# SDP_2.net
KiCad netlist of a schematic drawn in Altium Designer
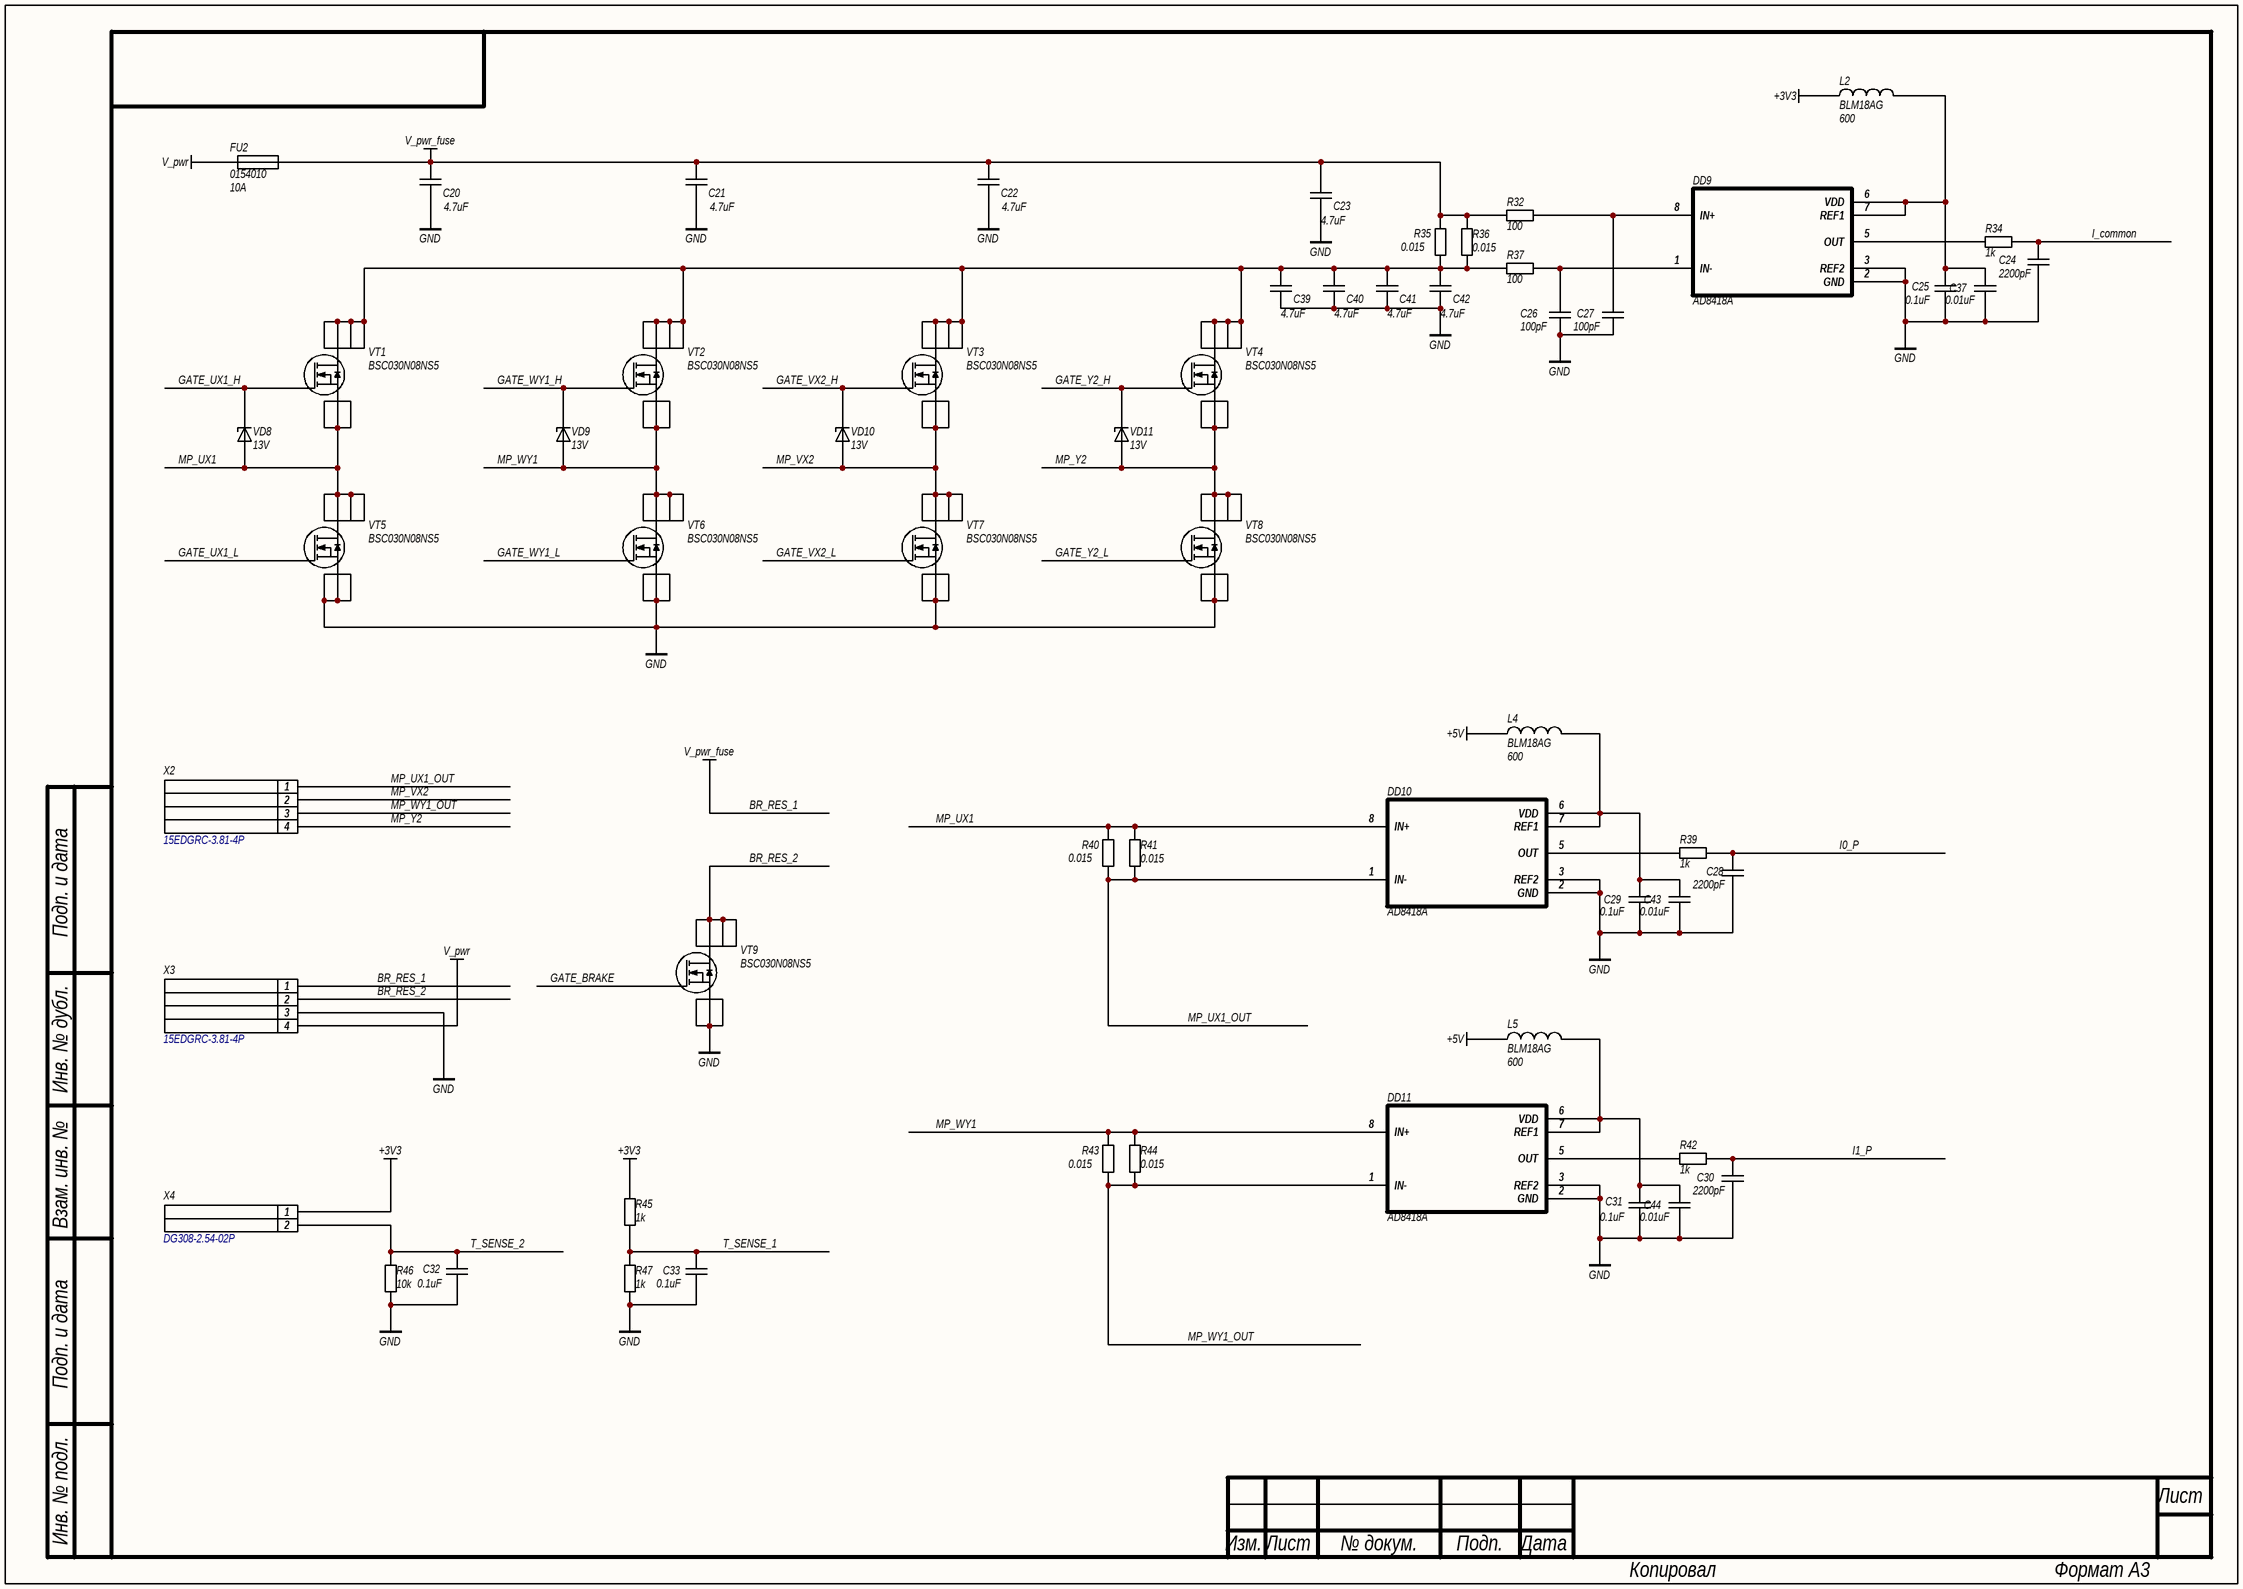
[diagram p0: SDP_2.SchDoc]

(export (version "E")
  (design (tool "Eeschema 10.0.6"))
  (components
    (comp (ref "C20")
      (value "4.7uF")
      (footprint "C1210")
      (description "SMD Capacitor")
      (fields (field (name "MANUFACTURER") "Murata") (field (name "TOLERANCE") "10%"))
      (libsource (lib "VKA") (part "CAP"))
    )
    (comp (ref "C21")
      (value "4.7uF")
      (footprint "C1210")
      (description "SMD Capacitor")
      (fields (field (name "MANUFACTURER") "Murata") (field (name "TOLERANCE") "10%"))
      (libsource (lib "VKA") (part "CAP"))
    )
    (comp (ref "C22")
      (value "4.7uF")
      (footprint "C1210")
      (description "SMD Capacitor")
      (fields (field (name "MANUFACTURER") "Murata") (field (name "TOLERANCE") "10%"))
      (libsource (lib "VKA") (part "CAP"))
    )
    (comp (ref "C23")
      (value "4.7uF")
      (footprint "C1210")
      (description "SMD Capacitor")
      (fields (field (name "MANUFACTURER") "Murata") (field (name "TOLERANCE") "10%"))
      (libsource (lib "VKA") (part "CAP"))
    )
    (comp (ref "C24")
      (value "2200pF")
      (footprint "C0603")
      (description "SMD Capacitor")
      (fields (field (name "MANUFACTURER") "Murata") (field (name "TOLERANCE") "10%"))
      (libsource (lib "VKA") (part "CAP"))
    )
    (comp (ref "C25")
      (value "0.1uF")
      (footprint "C0603")
      (description "SMD Capacitor")
      (fields (field (name "MANUFACTURER") "Murata") (field (name "TOLERANCE") "10%"))
      (libsource (lib "VKA") (part "CAP"))
    )
    (comp (ref "C26")
      (value "100pF")
      (footprint "C0603")
      (description "SMD Capacitor")
      (fields (field (name "MANUFACTURER") "Murata") (field (name "TOLERANCE") "10%"))
      (libsource (lib "VKA") (part "CAP"))
    )
    (comp (ref "C27")
      (value "100pF")
      (footprint "C0603")
      (description "SMD Capacitor")
      (fields (field (name "MANUFACTURER") "Murata") (field (name "TOLERANCE") "10%"))
      (libsource (lib "VKA") (part "CAP"))
    )
    (comp (ref "C28")
      (value "2200pF")
      (footprint "C0603")
      (description "SMD Capacitor")
      (fields (field (name "MANUFACTURER") "Murata") (field (name "TOLERANCE") "10%"))
      (libsource (lib "VKA") (part "CAP"))
    )
    (comp (ref "C29")
      (value "0.1uF")
      (footprint "C0603")
      (description "SMD Capacitor")
      (fields (field (name "MANUFACTURER") "Murata") (field (name "TOLERANCE") "10%"))
      (libsource (lib "VKA") (part "CAP"))
    )
    (comp (ref "C30")
      (value "2200pF")
      (footprint "C0603")
      (description "SMD Capacitor")
      (fields (field (name "MANUFACTURER") "Murata") (field (name "TOLERANCE") "10%"))
      (libsource (lib "VKA") (part "CAP"))
    )
    (comp (ref "C31")
      (value "0.1uF")
      (footprint "C0603")
      (description "SMD Capacitor")
      (fields (field (name "MANUFACTURER") "Murata") (field (name "TOLERANCE") "10%"))
      (libsource (lib "VKA") (part "CAP"))
    )
    (comp (ref "C32")
      (value "0.1uF")
      (footprint "C0603")
      (description "SMD Capacitor")
      (fields (field (name "MANUFACTURER") "Murata") (field (name "TOLERANCE") "10%"))
      (libsource (lib "VKA") (part "CAP"))
    )
    (comp (ref "C33")
      (value "0.1uF")
      (footprint "C0603")
      (description "SMD Capacitor")
      (fields (field (name "MANUFACTURER") "Murata") (field (name "TOLERANCE") "10%"))
      (libsource (lib "VKA") (part "CAP"))
    )
    (comp (ref "C37")
      (value "0.01uF")
      (footprint "C0603")
      (description "SMD Capacitor")
      (fields (field (name "MANUFACTURER") "Murata") (field (name "TOLERANCE") "10%"))
      (libsource (lib "VKA") (part "CAP"))
    )
    (comp (ref "C39")
      (value "4.7uF")
      (footprint "C1210")
      (description "SMD Capacitor")
      (fields (field (name "MANUFACTURER") "Murata") (field (name "TOLERANCE") "10%"))
      (libsource (lib "VKA") (part "CAP"))
    )
    (comp (ref "C40")
      (value "4.7uF")
      (footprint "C1210")
      (description "SMD Capacitor")
      (fields (field (name "MANUFACTURER") "Murata") (field (name "TOLERANCE") "10%"))
      (libsource (lib "VKA") (part "CAP"))
    )
    (comp (ref "C41")
      (value "4.7uF")
      (footprint "C1210")
      (description "SMD Capacitor")
      (fields (field (name "MANUFACTURER") "Murata") (field (name "TOLERANCE") "10%"))
      (libsource (lib "VKA") (part "CAP"))
    )
    (comp (ref "C42")
      (value "4.7uF")
      (footprint "C1210")
      (description "SMD Capacitor")
      (fields (field (name "MANUFACTURER") "Murata") (field (name "TOLERANCE") "10%"))
      (libsource (lib "VKA") (part "CAP"))
    )
    (comp (ref "C43")
      (value "0.01uF")
      (footprint "C0603")
      (description "SMD Capacitor")
      (fields (field (name "MANUFACTURER") "Murata") (field (name "TOLERANCE") "10%"))
      (libsource (lib "VKA") (part "CAP"))
    )
    (comp (ref "C44")
      (value "0.01uF")
      (footprint "C0603")
      (description "SMD Capacitor")
      (fields (field (name "MANUFACTURER") "Murata") (field (name "TOLERANCE") "10%"))
      (libsource (lib "VKA") (part "CAP"))
    )
    (comp (ref "DD9") (value "AD8418A") (footprint "MSOP8") (libsource (lib "DSP") (part "AD8418ABRMZ")))
    (comp (ref "DD10") (value "AD8418A") (footprint "MSOP8") (libsource (lib "DSP") (part "AD8418ABRMZ")))
    (comp (ref "DD11") (value "AD8418A") (footprint "MSOP8") (libsource (lib "DSP") (part "AD8418ABRMZ")))
    (comp (ref "FU2")
      (value "0154010")
      (footprint "omni_block_154")
      (description "omni fuse block")
      (fields (field (name "CURRENT") "10A"))
      (libsource (lib "DSP") (part "0154010"))
    )
    (comp (ref "L2")
      (value "BLM18AG")
      (footprint "R0603")
      (fields (field (name "ALTIUM_VALUE") "600"))
      (libsource (lib "VKA") (part "BLM18AG"))
    )
    (comp (ref "L4")
      (value "BLM18AG")
      (footprint "R0603")
      (fields (field (name "ALTIUM_VALUE") "600"))
      (libsource (lib "VKA") (part "BLM18AG"))
    )
    (comp (ref "L5")
      (value "BLM18AG")
      (footprint "R0603")
      (fields (field (name "ALTIUM_VALUE") "600"))
      (libsource (lib "VKA") (part "BLM18AG"))
    )
    (comp (ref "R32")
      (value "100")
      (footprint "R0603")
      (description "SMD Resistor")
      (fields (field (name "POWER") "0.062 Wt") (field (name "TOLERANCE") "5%"))
      (libsource (lib "") (part "RES_1"))
    )
    (comp (ref "R34")
      (value "1k")
      (footprint "R0603")
      (description "SMD Resistor")
      (fields (field (name "POWER") "0.062 Wt") (field (name "TOLERANCE") "5%"))
      (libsource (lib "") (part "RES_1"))
    )
    (comp (ref "R35")
      (value "0.015")
      (footprint "R2512")
      (description "SMD Resistor")
      (fields (field (name "POWER") "1 W") (field (name "TOLERANCE") "5%"))
      (libsource (lib "VKA") (part "RES2512"))
    )
    (comp (ref "R36")
      (value "0.015")
      (footprint "R2512")
      (description "SMD Resistor")
      (fields (field (name "POWER") "1 W") (field (name "TOLERANCE") "5%"))
      (libsource (lib "VKA") (part "RES2512"))
    )
    (comp (ref "R37")
      (value "100")
      (footprint "R0603")
      (description "SMD Resistor")
      (fields (field (name "POWER") "0.062 Wt") (field (name "TOLERANCE") "5%"))
      (libsource (lib "") (part "RES_1"))
    )
    (comp (ref "R39")
      (value "1k")
      (footprint "R0603")
      (description "SMD Resistor")
      (fields (field (name "POWER") "0.062 Wt") (field (name "TOLERANCE") "5%"))
      (libsource (lib "") (part "RES_1"))
    )
    (comp (ref "R40")
      (value "0.015")
      (footprint "R2512")
      (description "SMD Resistor")
      (fields (field (name "POWER") "1 W") (field (name "TOLERANCE") "5%"))
      (libsource (lib "VKA") (part "RES2512"))
    )
    (comp (ref "R41")
      (value "0.015")
      (footprint "R2512")
      (description "SMD Resistor")
      (fields (field (name "POWER") "1 W") (field (name "TOLERANCE") "5%"))
      (libsource (lib "VKA") (part "RES2512"))
    )
    (comp (ref "R42")
      (value "1k")
      (footprint "R0603")
      (description "SMD Resistor")
      (fields (field (name "POWER") "0.062 Wt") (field (name "TOLERANCE") "5%"))
      (libsource (lib "") (part "RES_1"))
    )
    (comp (ref "R43")
      (value "0.015")
      (footprint "R2512")
      (description "SMD Resistor")
      (fields (field (name "POWER") "1 W") (field (name "TOLERANCE") "5%"))
      (libsource (lib "VKA") (part "RES2512"))
    )
    (comp (ref "R44")
      (value "0.015")
      (footprint "R2512")
      (description "SMD Resistor")
      (fields (field (name "POWER") "1 W") (field (name "TOLERANCE") "5%"))
      (libsource (lib "VKA") (part "RES2512"))
    )
    (comp (ref "R45")
      (value "1k")
      (footprint "R0603")
      (description "SMD Resistor")
      (fields (field (name "POWER") "0.062 Wt") (field (name "TOLERANCE") "5%"))
      (libsource (lib "VKA") (part "RES"))
    )
    (comp (ref "R46")
      (value "10k")
      (footprint "R0603")
      (description "SMD Resistor")
      (fields (field (name "POWER") "0.062 Wt") (field (name "TOLERANCE") "5%"))
      (libsource (lib "VKA") (part "RES"))
    )
    (comp (ref "R47")
      (value "1k")
      (footprint "R0603")
      (description "SMD Resistor")
      (fields (field (name "POWER") "0.062 Wt") (field (name "TOLERANCE") "5%"))
      (libsource (lib "VKA") (part "RES"))
    )
    (comp (ref "VD8")
      (value "BZX384")
      (footprint "SOD323")
      (fields (field (name "VOLTAGE") "13V"))
      (libsource (lib "VKA") (part "BZX384"))
    )
    (comp (ref "VD9")
      (value "BZX384")
      (footprint "SOD323")
      (fields (field (name "VOLTAGE") "13V"))
      (libsource (lib "VKA") (part "BZX384"))
    )
    (comp (ref "VD10")
      (value "BZX384")
      (footprint "SOD323")
      (fields (field (name "VOLTAGE") "13V"))
      (libsource (lib "VKA") (part "BZX384"))
    )
    (comp (ref "VD11")
      (value "BZX384")
      (footprint "SOD323")
      (fields (field (name "VOLTAGE") "13V"))
      (libsource (lib "VKA") (part "BZX384"))
    )
    (comp (ref "VT1")
      (value "BSC030N08NS5")
      (footprint "TDSON-8")
      (description "MOSFET-N")
      (libsource (lib "DSP") (part "BSC030N08NS5"))
    )
    (comp (ref "VT2")
      (value "BSC030N08NS5")
      (footprint "TDSON-8")
      (description "MOSFET-N")
      (libsource (lib "DSP") (part "BSC030N08NS5"))
    )
    (comp (ref "VT3")
      (value "BSC030N08NS5")
      (footprint "TDSON-8")
      (description "MOSFET-N")
      (libsource (lib "DSP") (part "BSC030N08NS5"))
    )
    (comp (ref "VT4")
      (value "BSC030N08NS5")
      (footprint "TDSON-8")
      (description "MOSFET-N")
      (libsource (lib "DSP") (part "BSC030N08NS5"))
    )
    (comp (ref "VT5")
      (value "BSC030N08NS5")
      (footprint "TDSON-8")
      (description "MOSFET-N")
      (libsource (lib "DSP") (part "BSC030N08NS5"))
    )
    (comp (ref "VT6")
      (value "BSC030N08NS5")
      (footprint "TDSON-8")
      (description "MOSFET-N")
      (libsource (lib "DSP") (part "BSC030N08NS5"))
    )
    (comp (ref "VT7")
      (value "BSC030N08NS5")
      (footprint "TDSON-8")
      (description "MOSFET-N")
      (libsource (lib "DSP") (part "BSC030N08NS5"))
    )
    (comp (ref "VT8")
      (value "BSC030N08NS5")
      (footprint "TDSON-8")
      (description "MOSFET-N")
      (libsource (lib "DSP") (part "BSC030N08NS5"))
    )
    (comp (ref "VT9")
      (value "BSC030N08NS5")
      (footprint "TDSON-8")
      (description "MOSFET-N")
      (libsource (lib "DSP") (part "BSC030N08NS5"))
    )
    (comp (ref "X2")
      (value "15EDGRC-3.81-4P")
      (footprint "15EDGRC")
      (libsource (lib "DSP") (part "15EDGRC-3.81-4P"))
    )
    (comp (ref "X3")
      (value "15EDGRC-3.81-4P")
      (footprint "15EDGRC")
      (libsource (lib "DSP") (part "15EDGRC-3.81-4P"))
    )
    (comp (ref "X4")
      (value "DG308-2.54-02P")
      (footprint "DG308-2.54-2")
      (libsource (lib "DSP") (part "DG308-2.54-02P"))
    )
  )
  (nets
    (net (code "1") (name "+3V3") (class "Default")
      (node (ref "L2") (pin "1") (pinfunction "1_1") (pintype "passive"))
      (node (ref "R45") (pin "2") (pinfunction "2_2") (pintype "passive"))
      (node (ref "X4") (pin "1") (pinfunction "1_1") (pintype "passive"))
    )
    (net (code "2") (name "+5V") (class "Default")
      (node (ref "L4") (pin "1") (pinfunction "1_1") (pintype "passive"))
      (node (ref "L5") (pin "1") (pinfunction "1_1") (pintype "passive"))
    )
    (net (code "3") (name "/BR_RES_2") (class "Default")
      (node (ref "VT9") (pin "5") (pinfunction "D_5") (pintype "passive"))
      (node (ref "VT9") (pin "6") (pinfunction "D_6") (pintype "passive"))
      (node (ref "VT9") (pin "7") (pinfunction "D_7") (pintype "passive"))
      (node (ref "VT9") (pin "8") (pinfunction "D_8") (pintype "passive"))
      (node (ref "X3") (pin "2") (pinfunction "2_2") (pintype "passive"))
    )
    (net (code "4") (name "/GATE_BRAKE") (class "Default")
      (node (ref "VT9") (pin "4") (pinfunction "G_4") (pintype "passive"))
    )
    (net (code "5") (name "/GATE_UX1_H") (class "Default")
      (node (ref "VD8") (pin "2") (pinfunction "K_2") (pintype "passive"))
      (node (ref "VT1") (pin "4") (pinfunction "G_4") (pintype "passive"))
    )
    (net (code "6") (name "/GATE_UX1_L") (class "Default")
      (node (ref "VT5") (pin "4") (pinfunction "G_4") (pintype "passive"))
    )
    (net (code "7") (name "/GATE_VX2_H") (class "Default")
      (node (ref "VD10") (pin "2") (pinfunction "K_2") (pintype "passive"))
      (node (ref "VT3") (pin "4") (pinfunction "G_4") (pintype "passive"))
    )
    (net (code "8") (name "/GATE_VX2_L") (class "Default")
      (node (ref "VT7") (pin "4") (pinfunction "G_4") (pintype "passive"))
    )
    (net (code "9") (name "/GATE_WY1_H") (class "Default")
      (node (ref "VD9") (pin "2") (pinfunction "K_2") (pintype "passive"))
      (node (ref "VT2") (pin "4") (pinfunction "G_4") (pintype "passive"))
    )
    (net (code "10") (name "/GATE_WY1_L") (class "Default")
      (node (ref "VT6") (pin "4") (pinfunction "G_4") (pintype "passive"))
    )
    (net (code "11") (name "/GATE_Y2_H") (class "Default")
      (node (ref "VD11") (pin "2") (pinfunction "K_2") (pintype "passive"))
      (node (ref "VT4") (pin "4") (pinfunction "G_4") (pintype "passive"))
    )
    (net (code "12") (name "/GATE_Y2_L") (class "Default")
      (node (ref "VT8") (pin "4") (pinfunction "G_4") (pintype "passive"))
    )
    (net (code "13") (name "/I0_P") (class "Default")
      (node (ref "C28") (pin "2") (pinfunction "2_2") (pintype "passive"))
      (node (ref "R39") (pin "2") (pinfunction "2_2") (pintype "passive"))
    )
    (net (code "14") (name "/I1_P") (class "Default")
      (node (ref "C30") (pin "2") (pinfunction "2_2") (pintype "passive"))
      (node (ref "R42") (pin "2") (pinfunction "2_2") (pintype "passive"))
    )
    (net (code "15") (name "/I_common") (class "Default")
      (node (ref "C24") (pin "2") (pinfunction "2_2") (pintype "passive"))
      (node (ref "R34") (pin "2") (pinfunction "2_2") (pintype "passive"))
    )
    (net (code "16") (name "/MP_UX1") (class "Default")
      (node (ref "DD10") (pin "8") (pinfunction "IN+_8") (pintype "passive"))
      (node (ref "R40") (pin "2") (pinfunction "2_2") (pintype "passive"))
      (node (ref "R41") (pin "2") (pinfunction "2_2") (pintype "passive"))
      (node (ref "VD8") (pin "1") (pinfunction "A_1") (pintype "passive"))
      (node (ref "VT1") (pin "1") (pinfunction "S_1") (pintype "passive"))
      (node (ref "VT1") (pin "2") (pinfunction "S_2") (pintype "passive"))
      (node (ref "VT1") (pin "3") (pinfunction "S_3") (pintype "passive"))
      (node (ref "VT5") (pin "5") (pinfunction "D_5") (pintype "passive"))
      (node (ref "VT5") (pin "6") (pinfunction "D_6") (pintype "passive"))
      (node (ref "VT5") (pin "7") (pinfunction "D_7") (pintype "passive"))
      (node (ref "VT5") (pin "8") (pinfunction "D_8") (pintype "passive"))
    )
    (net (code "17") (name "/MP_UX1_OUT") (class "Default")
      (node (ref "DD10") (pin "1") (pinfunction "IN-_1") (pintype "passive"))
      (node (ref "R40") (pin "1") (pinfunction "1_1") (pintype "passive"))
      (node (ref "R41") (pin "1") (pinfunction "1_1") (pintype "passive"))
      (node (ref "X2") (pin "1") (pinfunction "1_1") (pintype "passive"))
    )
    (net (code "18") (name "/MP_VX2") (class "Default")
      (node (ref "VD10") (pin "1") (pinfunction "A_1") (pintype "passive"))
      (node (ref "VT3") (pin "1") (pinfunction "S_1") (pintype "passive"))
      (node (ref "VT3") (pin "2") (pinfunction "S_2") (pintype "passive"))
      (node (ref "VT3") (pin "3") (pinfunction "S_3") (pintype "passive"))
      (node (ref "VT7") (pin "5") (pinfunction "D_5") (pintype "passive"))
      (node (ref "VT7") (pin "6") (pinfunction "D_6") (pintype "passive"))
      (node (ref "VT7") (pin "7") (pinfunction "D_7") (pintype "passive"))
      (node (ref "VT7") (pin "8") (pinfunction "D_8") (pintype "passive"))
      (node (ref "X2") (pin "2") (pinfunction "2_2") (pintype "passive"))
    )
    (net (code "19") (name "/MP_WY1") (class "Default")
      (node (ref "DD11") (pin "8") (pinfunction "IN+_8") (pintype "passive"))
      (node (ref "R43") (pin "2") (pinfunction "2_2") (pintype "passive"))
      (node (ref "R44") (pin "2") (pinfunction "2_2") (pintype "passive"))
      (node (ref "VD9") (pin "1") (pinfunction "A_1") (pintype "passive"))
      (node (ref "VT2") (pin "1") (pinfunction "S_1") (pintype "passive"))
      (node (ref "VT2") (pin "2") (pinfunction "S_2") (pintype "passive"))
      (node (ref "VT2") (pin "3") (pinfunction "S_3") (pintype "passive"))
      (node (ref "VT6") (pin "5") (pinfunction "D_5") (pintype "passive"))
      (node (ref "VT6") (pin "6") (pinfunction "D_6") (pintype "passive"))
      (node (ref "VT6") (pin "7") (pinfunction "D_7") (pintype "passive"))
      (node (ref "VT6") (pin "8") (pinfunction "D_8") (pintype "passive"))
    )
    (net (code "20") (name "/MP_WY1_OUT") (class "Default")
      (node (ref "DD11") (pin "1") (pinfunction "IN-_1") (pintype "passive"))
      (node (ref "R43") (pin "1") (pinfunction "1_1") (pintype "passive"))
      (node (ref "R44") (pin "1") (pinfunction "1_1") (pintype "passive"))
      (node (ref "X2") (pin "3") (pinfunction "3_3") (pintype "passive"))
    )
    (net (code "21") (name "/MP_Y2") (class "Default")
      (node (ref "VD11") (pin "1") (pinfunction "A_1") (pintype "passive"))
      (node (ref "VT4") (pin "1") (pinfunction "S_1") (pintype "passive"))
      (node (ref "VT4") (pin "2") (pinfunction "S_2") (pintype "passive"))
      (node (ref "VT4") (pin "3") (pinfunction "S_3") (pintype "passive"))
      (node (ref "VT8") (pin "5") (pinfunction "D_5") (pintype "passive"))
      (node (ref "VT8") (pin "6") (pinfunction "D_6") (pintype "passive"))
      (node (ref "VT8") (pin "7") (pinfunction "D_7") (pintype "passive"))
      (node (ref "VT8") (pin "8") (pinfunction "D_8") (pintype "passive"))
      (node (ref "X2") (pin "4") (pinfunction "4_4") (pintype "passive"))
    )
    (net (code "22") (name "/T_SENSE_1") (class "Default")
      (node (ref "C33") (pin "2") (pinfunction "2_2") (pintype "passive"))
      (node (ref "R45") (pin "1") (pinfunction "1_1") (pintype "passive"))
      (node (ref "R47") (pin "2") (pinfunction "2_2") (pintype "passive"))
    )
    (net (code "23") (name "/T_SENSE_2") (class "Default")
      (node (ref "C32") (pin "2") (pinfunction "2_2") (pintype "passive"))
      (node (ref "R46") (pin "2") (pinfunction "2_2") (pintype "passive"))
      (node (ref "X4") (pin "2") (pinfunction "2_2") (pintype "passive"))
    )
    (net (code "24") (name "GND") (class "Default")
      (node (ref "C20") (pin "1") (pinfunction "1_1") (pintype "passive"))
      (node (ref "C21") (pin "1") (pinfunction "1_1") (pintype "passive"))
      (node (ref "C22") (pin "1") (pinfunction "1_1") (pintype "passive"))
      (node (ref "C23") (pin "1") (pinfunction "1_1") (pintype "passive"))
      (node (ref "C24") (pin "1") (pinfunction "1_1") (pintype "passive"))
      (node (ref "C25") (pin "1") (pinfunction "1_1") (pintype "passive"))
      (node (ref "C26") (pin "1") (pinfunction "1_1") (pintype "passive"))
      (node (ref "C27") (pin "1") (pinfunction "1_1") (pintype "passive"))
      (node (ref "C28") (pin "1") (pinfunction "1_1") (pintype "passive"))
      (node (ref "C29") (pin "1") (pinfunction "1_1") (pintype "passive"))
      (node (ref "C30") (pin "1") (pinfunction "1_1") (pintype "passive"))
      (node (ref "C31") (pin "1") (pinfunction "1_1") (pintype "passive"))
      (node (ref "C32") (pin "1") (pinfunction "1_1") (pintype "passive"))
      (node (ref "C33") (pin "1") (pinfunction "1_1") (pintype "passive"))
      (node (ref "C37") (pin "1") (pinfunction "1_1") (pintype "passive"))
      (node (ref "C39") (pin "1") (pinfunction "1_1") (pintype "passive"))
      (node (ref "C40") (pin "1") (pinfunction "1_1") (pintype "passive"))
      (node (ref "C41") (pin "1") (pinfunction "1_1") (pintype "passive"))
      (node (ref "C42") (pin "1") (pinfunction "1_1") (pintype "passive"))
      (node (ref "C43") (pin "1") (pinfunction "1_1") (pintype "passive"))
      (node (ref "C44") (pin "1") (pinfunction "1_1") (pintype "passive"))
      (node (ref "DD10") (pin "2") (pinfunction "GND_2") (pintype "passive"))
      (node (ref "DD10") (pin "3") (pinfunction "REF2_3") (pintype "passive"))
      (node (ref "DD11") (pin "2") (pinfunction "GND_2") (pintype "passive"))
      (node (ref "DD11") (pin "3") (pinfunction "REF2_3") (pintype "passive"))
      (node (ref "DD9") (pin "2") (pinfunction "GND_2") (pintype "passive"))
      (node (ref "DD9") (pin "3") (pinfunction "REF2_3") (pintype "passive"))
      (node (ref "R46") (pin "1") (pinfunction "1_1") (pintype "passive"))
      (node (ref "R47") (pin "1") (pinfunction "1_1") (pintype "passive"))
      (node (ref "VT5") (pin "1") (pinfunction "S_1") (pintype "passive"))
      (node (ref "VT5") (pin "2") (pinfunction "S_2") (pintype "passive"))
      (node (ref "VT5") (pin "3") (pinfunction "S_3") (pintype "passive"))
      (node (ref "VT6") (pin "1") (pinfunction "S_1") (pintype "passive"))
      (node (ref "VT6") (pin "2") (pinfunction "S_2") (pintype "passive"))
      (node (ref "VT6") (pin "3") (pinfunction "S_3") (pintype "passive"))
      (node (ref "VT7") (pin "1") (pinfunction "S_1") (pintype "passive"))
      (node (ref "VT7") (pin "2") (pinfunction "S_2") (pintype "passive"))
      (node (ref "VT7") (pin "3") (pinfunction "S_3") (pintype "passive"))
      (node (ref "VT8") (pin "1") (pinfunction "S_1") (pintype "passive"))
      (node (ref "VT8") (pin "2") (pinfunction "S_2") (pintype "passive"))
      (node (ref "VT8") (pin "3") (pinfunction "S_3") (pintype "passive"))
      (node (ref "VT9") (pin "1") (pinfunction "S_1") (pintype "passive"))
      (node (ref "VT9") (pin "2") (pinfunction "S_2") (pintype "passive"))
      (node (ref "VT9") (pin "3") (pinfunction "S_3") (pintype "passive"))
      (node (ref "X3") (pin "3") (pinfunction "3_3") (pintype "passive"))
    )
    (net (code "25") (name "Net-(C39-Pad2)") (class "Default")
      (node (ref "C39") (pin "2") (pinfunction "2_2") (pintype "passive"))
      (node (ref "C40") (pin "2") (pinfunction "2_2") (pintype "passive"))
      (node (ref "C41") (pin "2") (pinfunction "2_2") (pintype "passive"))
      (node (ref "C42") (pin "2") (pinfunction "2_2") (pintype "passive"))
      (node (ref "R35") (pin "1") (pinfunction "1_1") (pintype "passive"))
      (node (ref "R36") (pin "1") (pinfunction "1_1") (pintype "passive"))
      (node (ref "R37") (pin "1") (pinfunction "1_1") (pintype "passive"))
      (node (ref "VT1") (pin "5") (pinfunction "D_5") (pintype "passive"))
      (node (ref "VT1") (pin "6") (pinfunction "D_6") (pintype "passive"))
      (node (ref "VT1") (pin "7") (pinfunction "D_7") (pintype "passive"))
      (node (ref "VT1") (pin "8") (pinfunction "D_8") (pintype "passive"))
      (node (ref "VT2") (pin "5") (pinfunction "D_5") (pintype "passive"))
      (node (ref "VT2") (pin "6") (pinfunction "D_6") (pintype "passive"))
      (node (ref "VT2") (pin "7") (pinfunction "D_7") (pintype "passive"))
      (node (ref "VT2") (pin "8") (pinfunction "D_8") (pintype "passive"))
      (node (ref "VT3") (pin "5") (pinfunction "D_5") (pintype "passive"))
      (node (ref "VT3") (pin "6") (pinfunction "D_6") (pintype "passive"))
      (node (ref "VT3") (pin "7") (pinfunction "D_7") (pintype "passive"))
      (node (ref "VT3") (pin "8") (pinfunction "D_8") (pintype "passive"))
      (node (ref "VT4") (pin "5") (pinfunction "D_5") (pintype "passive"))
      (node (ref "VT4") (pin "6") (pinfunction "D_6") (pintype "passive"))
      (node (ref "VT4") (pin "7") (pinfunction "D_7") (pintype "passive"))
      (node (ref "VT4") (pin "8") (pinfunction "D_8") (pintype "passive"))
    )
    (net (code "26") (name "Net-(DD9-IN+)") (class "Default")
      (node (ref "C27") (pin "2") (pinfunction "2_2") (pintype "passive"))
      (node (ref "DD9") (pin "8") (pinfunction "IN+_8") (pintype "passive"))
      (node (ref "R32") (pin "2") (pinfunction "2_2") (pintype "passive"))
    )
    (net (code "27") (name "Net-(DD9-IN-)") (class "Default")
      (node (ref "C26") (pin "2") (pinfunction "2_2") (pintype "passive"))
      (node (ref "DD9") (pin "1") (pinfunction "IN-_1") (pintype "passive"))
      (node (ref "R37") (pin "2") (pinfunction "2_2") (pintype "passive"))
    )
    (net (code "28") (name "Net-(DD9-OUT)") (class "Default")
      (node (ref "DD9") (pin "5") (pinfunction "OUT_5") (pintype "passive"))
      (node (ref "R34") (pin "1") (pinfunction "1_1") (pintype "passive"))
    )
    (net (code "29") (name "Net-(DD9-REF1)") (class "Default")
      (node (ref "C25") (pin "2") (pinfunction "2_2") (pintype "passive"))
      (node (ref "C37") (pin "2") (pinfunction "2_2") (pintype "passive"))
      (node (ref "DD9") (pin "6") (pinfunction "VDD_6") (pintype "passive"))
      (node (ref "DD9") (pin "7") (pinfunction "REF1_7") (pintype "passive"))
      (node (ref "L2") (pin "2") (pinfunction "2_2") (pintype "passive"))
    )
    (net (code "30") (name "Net-(DD10-OUT)") (class "Default")
      (node (ref "DD10") (pin "5") (pinfunction "OUT_5") (pintype "passive"))
      (node (ref "R39") (pin "1") (pinfunction "1_1") (pintype "passive"))
    )
    (net (code "31") (name "Net-(DD10-REF1)") (class "Default")
      (node (ref "C29") (pin "2") (pinfunction "2_2") (pintype "passive"))
      (node (ref "C43") (pin "2") (pinfunction "2_2") (pintype "passive"))
      (node (ref "DD10") (pin "6") (pinfunction "VDD_6") (pintype "passive"))
      (node (ref "DD10") (pin "7") (pinfunction "REF1_7") (pintype "passive"))
      (node (ref "L4") (pin "2") (pinfunction "2_2") (pintype "passive"))
    )
    (net (code "32") (name "Net-(DD11-OUT)") (class "Default")
      (node (ref "DD11") (pin "5") (pinfunction "OUT_5") (pintype "passive"))
      (node (ref "R42") (pin "1") (pinfunction "1_1") (pintype "passive"))
    )
    (net (code "33") (name "Net-(DD11-REF1)") (class "Default")
      (node (ref "C31") (pin "2") (pinfunction "2_2") (pintype "passive"))
      (node (ref "C44") (pin "2") (pinfunction "2_2") (pintype "passive"))
      (node (ref "DD11") (pin "6") (pinfunction "VDD_6") (pintype "passive"))
      (node (ref "DD11") (pin "7") (pinfunction "REF1_7") (pintype "passive"))
      (node (ref "L5") (pin "2") (pinfunction "2_2") (pintype "passive"))
    )
    (net (code "34") (name "V_pwr") (class "Default")
      (node (ref "FU2") (pin "1") (pinfunction "1_1") (pintype "passive"))
      (node (ref "X3") (pin "4") (pinfunction "4_4") (pintype "passive"))
    )
    (net (code "35") (name "V_pwr_fuse") (class "Default")
      (node (ref "C20") (pin "2") (pinfunction "2_2") (pintype "passive"))
      (node (ref "C21") (pin "2") (pinfunction "2_2") (pintype "passive"))
      (node (ref "C22") (pin "2") (pinfunction "2_2") (pintype "passive"))
      (node (ref "C23") (pin "2") (pinfunction "2_2") (pintype "passive"))
      (node (ref "FU2") (pin "2") (pinfunction "2_2") (pintype "passive"))
      (node (ref "R32") (pin "1") (pinfunction "1_1") (pintype "passive"))
      (node (ref "R35") (pin "2") (pinfunction "2_2") (pintype "passive"))
      (node (ref "R36") (pin "2") (pinfunction "2_2") (pintype "passive"))
      (node (ref "X3") (pin "1") (pinfunction "1_1") (pintype "passive"))
    )
  )
)
